# SCH_V1.net
KiCad netlist of a schematic drawn in Altium Designer
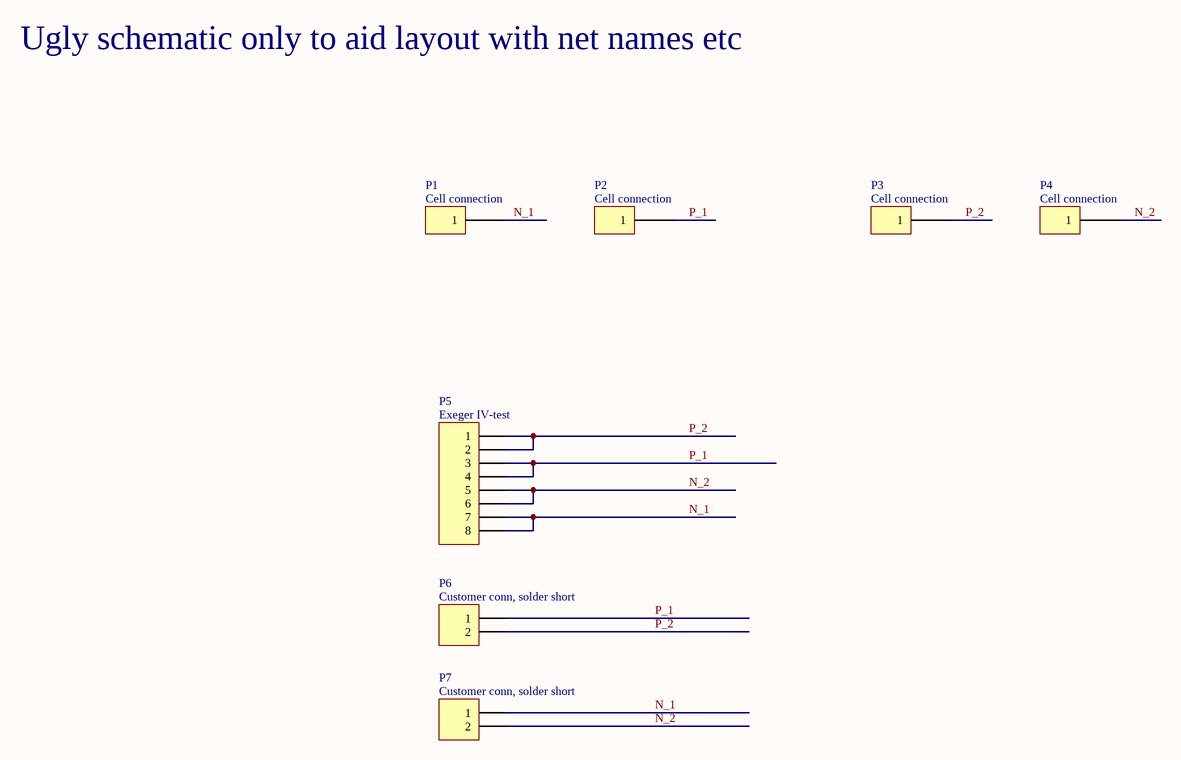
[diagram p0: SCH_V1.SchDoc]

(export (version "E")
  (design (tool "Eeschema 10.0.6"))
  (components
    (comp (ref "P1")
      (value "Cell connection")
      (footprint "Cell_pad_4mm_SM0.5mm")
      (libsource (lib "Flex_SCH_symbols") (part "Cell connection 1P"))
    )
    (comp (ref "P2")
      (value "Cell connection")
      (footprint "Cell_pad_4mm_SM0.5mm")
      (libsource (lib "Flex_SCH_symbols") (part "Cell connection 1P"))
    )
    (comp (ref "P3")
      (value "Cell connection")
      (footprint "Cell_pad_4mm_SM0.5mm")
      (libsource (lib "Flex_SCH_symbols") (part "Cell connection 1P"))
    )
    (comp (ref "P4")
      (value "Cell connection")
      (footprint "Cell_pad_4mm_SM0.5mm")
      (libsource (lib "Flex_SCH_symbols") (part "Cell connection 1P"))
    )
    (comp (ref "P5")
      (value "Exeger IV-test")
      (footprint "EXEGER_IV_8_PIN_NO_STIFF_ISOL_0.4")
      (description "Header, 8-Pin")
      (libsource (lib "Miscellaneous Connectors") (part "Header 8"))
    )
    (comp (ref "P6")
      (value "Customer conn, solder short")
      (footprint "Customer_2022_solder_short_ISOL_0.4_S")
      (description "Header, 2-Pin")
      (libsource (lib "Miscellaneous Connectors") (part "Header 2"))
    )
    (comp (ref "P7")
      (value "Customer conn, solder short")
      (footprint "Customer_2022_solder_short_ISOL_0.4_S")
      (description "Header, 2-Pin")
      (libsource (lib "Miscellaneous Connectors") (part "Header 2"))
    )
  )
  (nets
    (net (code "1") (name "/N_1") (class "Default")
      (node (ref "P1") (pin "1") (pinfunction "1_1") (pintype "passive"))
      (node (ref "P5") (pin "7") (pinfunction "7_7") (pintype "passive"))
      (node (ref "P5") (pin "8") (pinfunction "8_8") (pintype "passive"))
      (node (ref "P7") (pin "1") (pinfunction "1_1") (pintype "passive"))
    )
    (net (code "2") (name "/N_2") (class "Default")
      (node (ref "P4") (pin "1") (pinfunction "1_1") (pintype "passive"))
      (node (ref "P5") (pin "5") (pinfunction "5_5") (pintype "passive"))
      (node (ref "P5") (pin "6") (pinfunction "6_6") (pintype "passive"))
      (node (ref "P7") (pin "2") (pinfunction "2_2") (pintype "passive"))
    )
    (net (code "3") (name "/P_1") (class "Default")
      (node (ref "P2") (pin "1") (pinfunction "1_1") (pintype "passive"))
      (node (ref "P5") (pin "3") (pinfunction "3_3") (pintype "passive"))
      (node (ref "P5") (pin "4") (pinfunction "4_4") (pintype "passive"))
      (node (ref "P6") (pin "1") (pinfunction "1_1") (pintype "passive"))
    )
    (net (code "4") (name "/P_2") (class "Default")
      (node (ref "P3") (pin "1") (pinfunction "1_1") (pintype "passive"))
      (node (ref "P5") (pin "1") (pinfunction "1_1") (pintype "passive"))
      (node (ref "P5") (pin "2") (pinfunction "2_2") (pintype "passive"))
      (node (ref "P6") (pin "2") (pinfunction "2_2") (pintype "passive"))
    )
  )
)
